# 1-Schematic_relay_module.net
KiCad netlist of a schematic drawn in EasyEDA
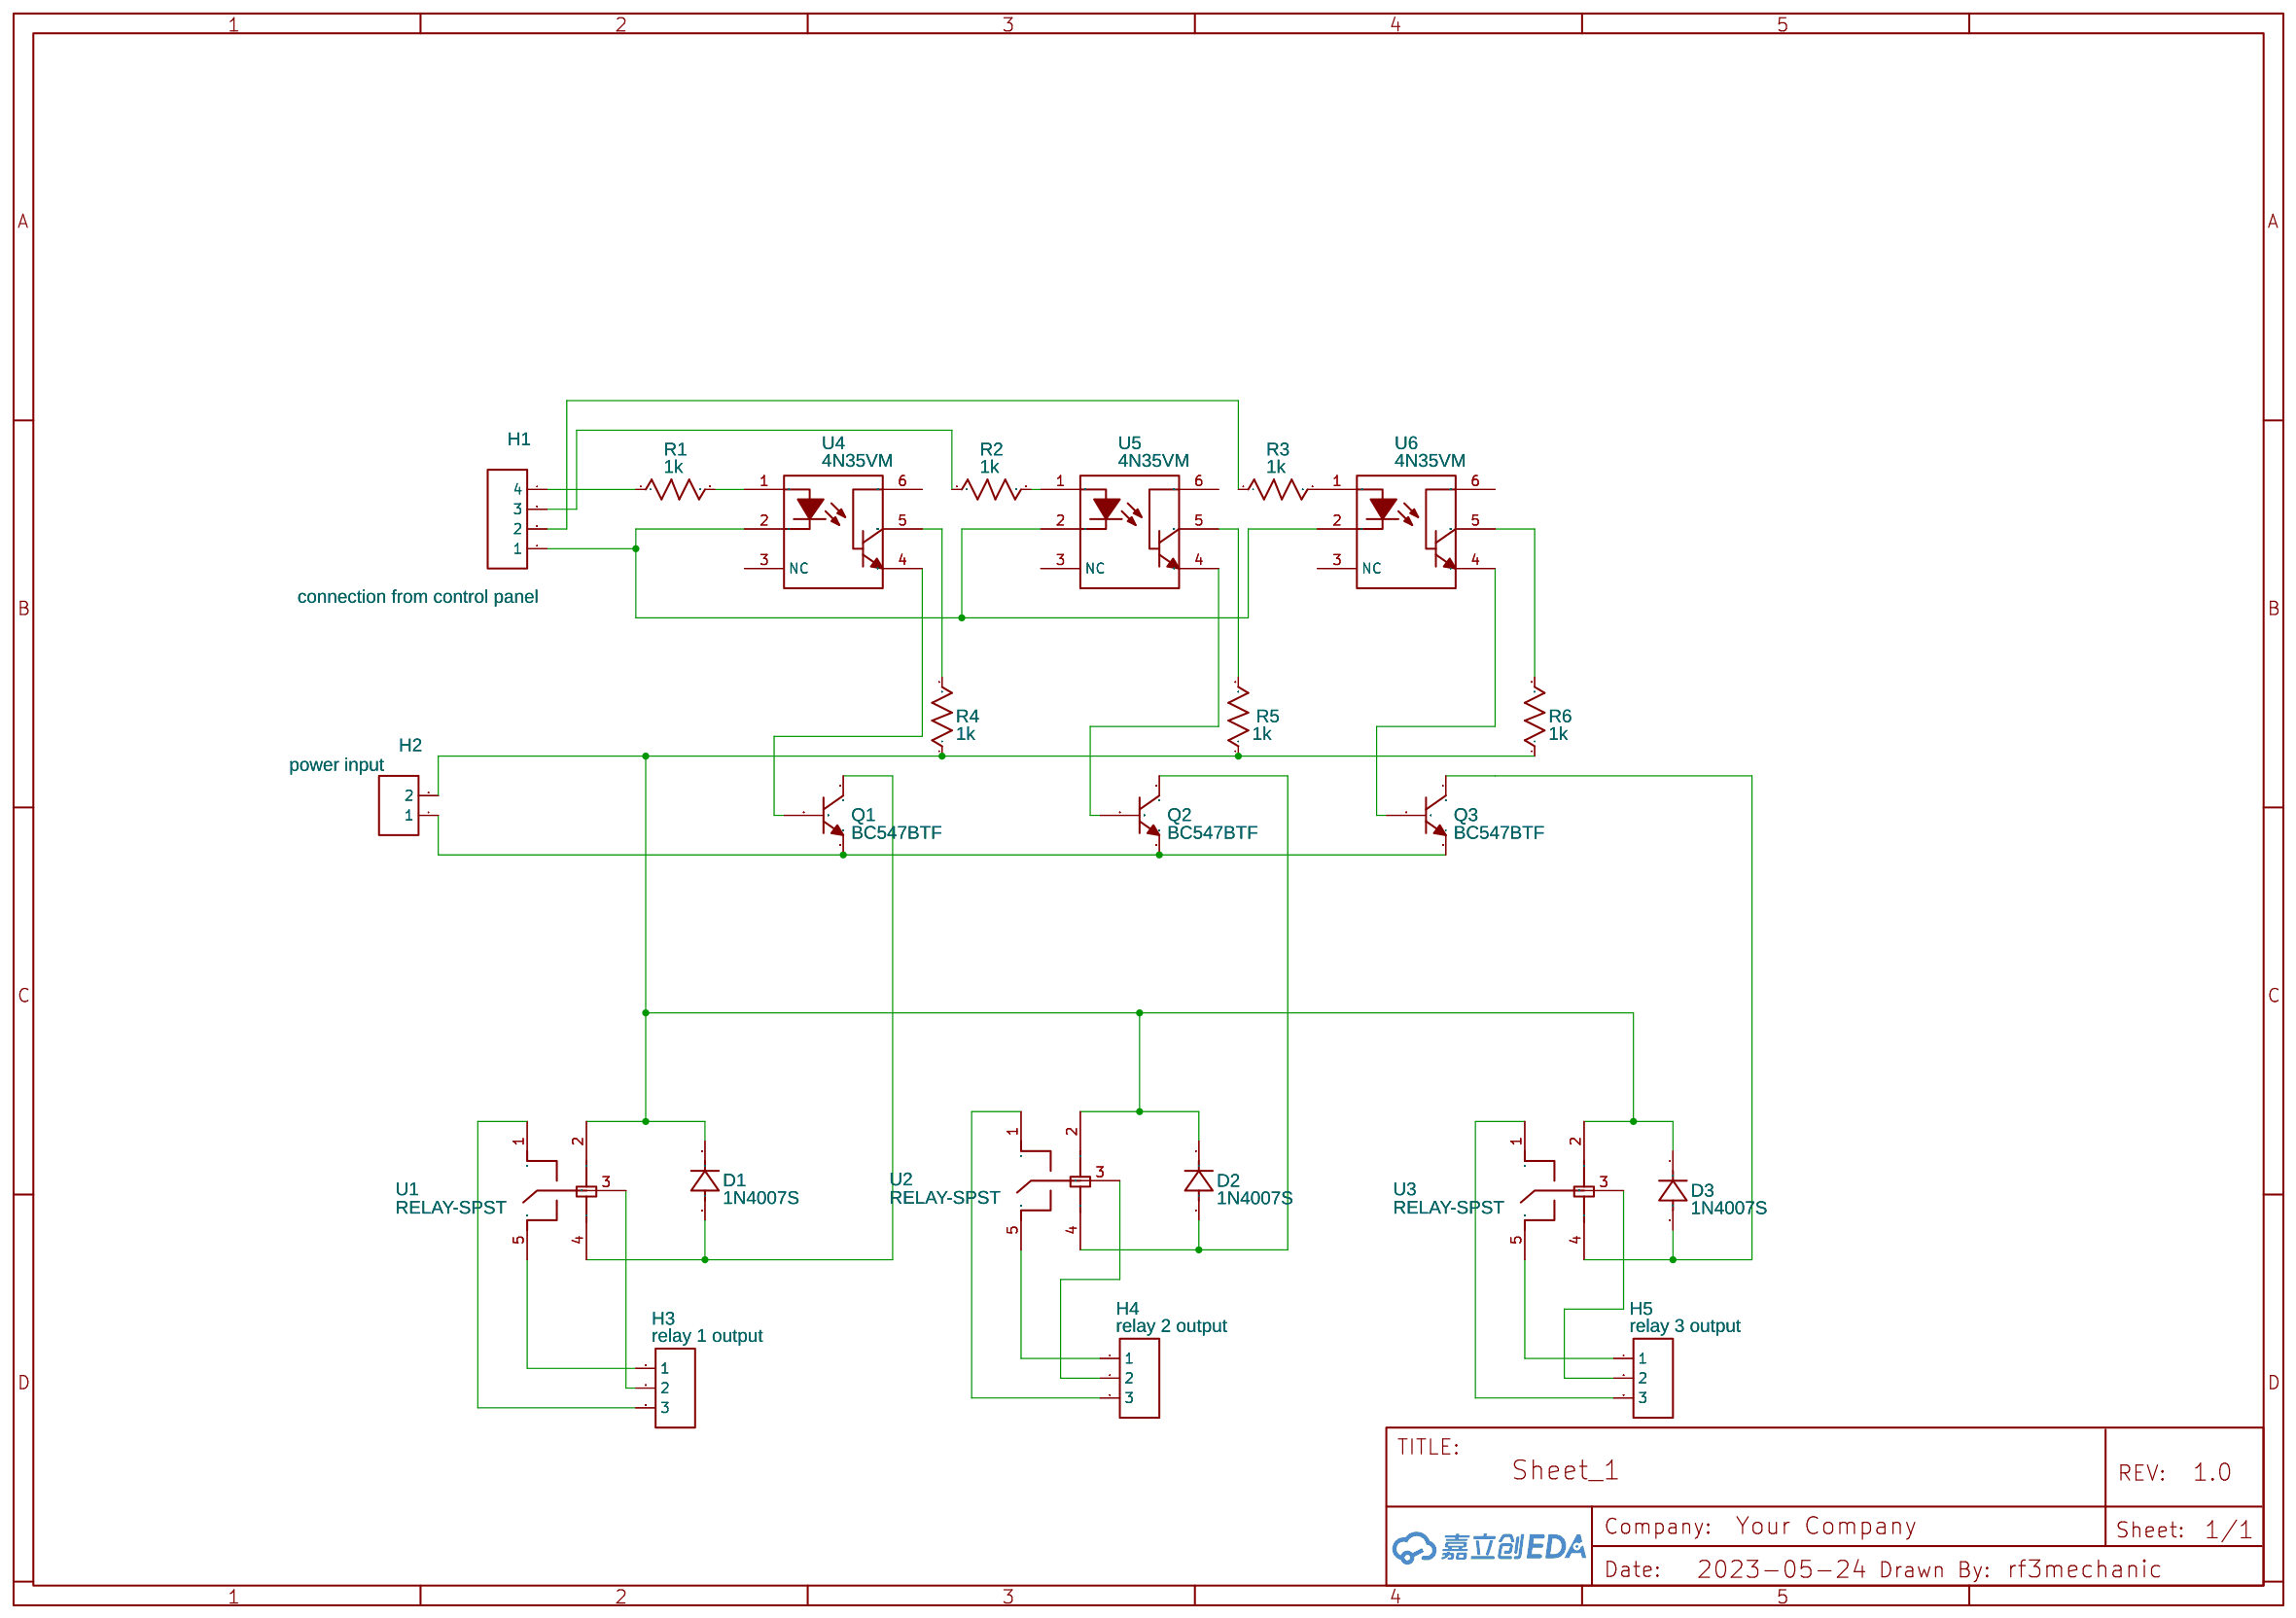
[diagram p0: schematic sheet]

(export (version "E")
  (design (tool "Eeschema 10.0.6"))
  (components
    (comp (ref "D1")
      (value "1N4007S")
      (fields (field (name "BOM_Supplier Part") "C2992088"))
      (libsource (lib "") (part "1N4007S"))
    )
    (comp (ref "D2")
      (value "1N4007S")
      (fields (field (name "BOM_Supplier Part") "C2992088"))
      (libsource (lib "") (part "1N4007S"))
    )
    (comp (ref "D3")
      (value "1N4007S")
      (fields (field (name "BOM_Supplier Part") "C2992088"))
      (libsource (lib "") (part "1N4007S"))
    )
    (comp (ref "H1")
      (value "connection from control panel")
      (fields (field (name "BOM_Supplier Part") "C225501"))
      (libsource (lib "") (part "HDR-F-2.54_1x4"))
    )
    (comp (ref "H2")
      (value "power input")
      (fields (field (name "BOM_Supplier Part") "C49661"))
      (libsource (lib "") (part "HDR-F-2.54_1x2"))
    )
    (comp (ref "H3")
      (value "relay 1 output")
      (fields (field (name "BOM_Supplier Part") "C146690"))
      (libsource (lib "") (part "HDR-F-2.54_1x3"))
    )
    (comp (ref "H4")
      (value "relay 2 output")
      (fields (field (name "BOM_Supplier Part") "C146690"))
      (libsource (lib "") (part "HDR-F-2.54_1x3"))
    )
    (comp (ref "H5")
      (value "relay 3 output")
      (fields (field (name "BOM_Supplier Part") "C146690"))
      (libsource (lib "") (part "HDR-F-2.54_1x3"))
    )
    (comp (ref "Q1")
      (value "BC547BTF")
      (fields (field (name "BOM_Supplier Part") "C900798"))
      (libsource (lib "") (part "BC547BTF"))
    )
    (comp (ref "Q2")
      (value "BC547BTF")
      (fields (field (name "BOM_Supplier Part") "C900798"))
      (libsource (lib "") (part "BC547BTF"))
    )
    (comp (ref "Q3")
      (value "BC547BTF")
      (fields (field (name "BOM_Supplier Part") "C900798"))
      (libsource (lib "") (part "BC547BTF"))
    )
    (comp (ref "R1") (value "1k") (libsource (lib "") (part "R_AXIAL-0.4_US")))
    (comp (ref "R2") (value "1k") (libsource (lib "") (part "R_AXIAL-0.4_US")))
    (comp (ref "R3") (value "1k") (libsource (lib "") (part "R_AXIAL-0.4_US")))
    (comp (ref "R4") (value "1k") (libsource (lib "") (part "R_AXIAL-0.4_US_1")))
    (comp (ref "R5") (value "1k") (libsource (lib "") (part "R_AXIAL-0.4_US_1")))
    (comp (ref "R6") (value "1k") (libsource (lib "") (part "R_AXIAL-0.4_US_1")))
    (comp (ref "U1")
      (value "RELAY-SPST")
      (fields
        (field (name "BOM_Manufacturer Part") "Relay-SPST")
        (field (name "BOM_Supplier Part") "C2941249")
      )
      (libsource (lib "") (part "RELAY-SPST"))
    )
    (comp (ref "U2")
      (value "RELAY-SPST")
      (fields
        (field (name "BOM_Manufacturer Part") "Relay-SPST")
        (field (name "BOM_Supplier Part") "C2941249")
      )
      (libsource (lib "") (part "RELAY-SPST"))
    )
    (comp (ref "U3")
      (value "RELAY-SPST")
      (fields
        (field (name "BOM_Manufacturer Part") "Relay-SPST")
        (field (name "BOM_Supplier Part") "C2941249")
      )
      (libsource (lib "") (part "RELAY-SPST"))
    )
    (comp (ref "U4")
      (value "4N35VM")
      (fields (field (name "BOM_Supplier Part") "C898968"))
      (libsource (lib "") (part "4N35VM"))
    )
    (comp (ref "U5")
      (value "4N35VM")
      (fields (field (name "BOM_Supplier Part") "C898968"))
      (libsource (lib "") (part "4N35VM"))
    )
    (comp (ref "U6")
      (value "4N35VM")
      (fields (field (name "BOM_Supplier Part") "C898968"))
      (libsource (lib "") (part "4N35VM"))
    )
  )
  (nets
    (net (code "1") (name "Net-(D1-A)") (class "Default")
      (node (ref "D1") (pin "2") (pinfunction "A_2") (pintype "unspecified"))
      (node (ref "Q1") (pin "1") (pinfunction "C_1") (pintype "unspecified"))
      (node (ref "U1") (pin "4") (pinfunction "4_4") (pintype "unspecified"))
    )
    (net (code "2") (name "Net-(D1-K)") (class "Default")
      (node (ref "D1") (pin "1") (pinfunction "K_1") (pintype "unspecified"))
      (node (ref "D2") (pin "1") (pinfunction "K_1") (pintype "unspecified"))
      (node (ref "D3") (pin "1") (pinfunction "K_1") (pintype "unspecified"))
      (node (ref "H2") (pin "2") (pinfunction "2_2") (pintype "input"))
      (node (ref "R4") (pin "1") (pinfunction "1_1") (pintype "unspecified"))
      (node (ref "R5") (pin "1") (pinfunction "1_1") (pintype "unspecified"))
      (node (ref "R6") (pin "1") (pinfunction "1_1") (pintype "unspecified"))
      (node (ref "U1") (pin "2") (pinfunction "2_2") (pintype "unspecified"))
      (node (ref "U2") (pin "2") (pinfunction "2_2") (pintype "unspecified"))
      (node (ref "U3") (pin "2") (pinfunction "2_2") (pintype "unspecified"))
    )
    (net (code "3") (name "Net-(D2-A)") (class "Default")
      (node (ref "D2") (pin "2") (pinfunction "A_2") (pintype "unspecified"))
      (node (ref "Q2") (pin "1") (pinfunction "C_1") (pintype "unspecified"))
      (node (ref "U2") (pin "4") (pinfunction "4_4") (pintype "unspecified"))
    )
    (net (code "4") (name "Net-(D3-A)") (class "Default")
      (node (ref "D3") (pin "2") (pinfunction "A_2") (pintype "unspecified"))
      (node (ref "Q3") (pin "1") (pinfunction "C_1") (pintype "unspecified"))
      (node (ref "U3") (pin "4") (pinfunction "4_4") (pintype "unspecified"))
    )
    (net (code "5") (name "Net-(H1-Pad2)") (class "Default")
      (node (ref "H1") (pin "2") (pinfunction "2_2") (pintype "unspecified"))
      (node (ref "R3") (pin "1") (pinfunction "1_1") (pintype "unspecified"))
    )
    (net (code "6") (name "Net-(H1-Pad3)") (class "Default")
      (node (ref "H1") (pin "3") (pinfunction "3_3") (pintype "unspecified"))
      (node (ref "R2") (pin "1") (pinfunction "1_1") (pintype "unspecified"))
    )
    (net (code "7") (name "Net-(H1-Pad4)") (class "Default")
      (node (ref "H1") (pin "4") (pinfunction "4_4") (pintype "unspecified"))
      (node (ref "R1") (pin "1") (pinfunction "1_1") (pintype "unspecified"))
    )
    (net (code "8") (name "Net-(H3-Pad1)") (class "Default")
      (node (ref "H3") (pin "1") (pinfunction "1_1") (pintype "input"))
      (node (ref "U1") (pin "5") (pinfunction "5_5") (pintype "unspecified"))
    )
    (net (code "9") (name "Net-(H3-Pad2)") (class "Default")
      (node (ref "H3") (pin "2") (pinfunction "2_2") (pintype "input"))
      (node (ref "U1") (pin "3") (pinfunction "3_3") (pintype "unspecified"))
    )
    (net (code "10") (name "Net-(H3-Pad3)") (class "Default")
      (node (ref "H3") (pin "3") (pinfunction "3_3") (pintype "input"))
      (node (ref "U1") (pin "1") (pinfunction "1_1") (pintype "unspecified"))
    )
    (net (code "11") (name "Net-(H4-Pad1)") (class "Default")
      (node (ref "H4") (pin "1") (pinfunction "1_1") (pintype "input"))
      (node (ref "U2") (pin "5") (pinfunction "5_5") (pintype "unspecified"))
    )
    (net (code "12") (name "Net-(H4-Pad2)") (class "Default")
      (node (ref "H4") (pin "2") (pinfunction "2_2") (pintype "input"))
      (node (ref "U2") (pin "3") (pinfunction "3_3") (pintype "unspecified"))
    )
    (net (code "13") (name "Net-(H4-Pad3)") (class "Default")
      (node (ref "H4") (pin "3") (pinfunction "3_3") (pintype "input"))
      (node (ref "U2") (pin "1") (pinfunction "1_1") (pintype "unspecified"))
    )
    (net (code "14") (name "Net-(H5-Pad1)") (class "Default")
      (node (ref "H5") (pin "1") (pinfunction "1_1") (pintype "input"))
      (node (ref "U3") (pin "5") (pinfunction "5_5") (pintype "unspecified"))
    )
    (net (code "15") (name "Net-(H5-Pad2)") (class "Default")
      (node (ref "H5") (pin "2") (pinfunction "2_2") (pintype "input"))
      (node (ref "U3") (pin "3") (pinfunction "3_3") (pintype "unspecified"))
    )
    (net (code "16") (name "Net-(H5-Pad3)") (class "Default")
      (node (ref "H5") (pin "3") (pinfunction "3_3") (pintype "input"))
      (node (ref "U3") (pin "1") (pinfunction "1_1") (pintype "unspecified"))
    )
    (net (code "17") (name "Net-(Q1-B)") (class "Default")
      (node (ref "Q1") (pin "2") (pinfunction "B_2") (pintype "unspecified"))
      (node (ref "U4") (pin "4") (pinfunction "EMI_4") (pintype "unspecified"))
    )
    (net (code "18") (name "Net-(Q1-E)") (class "Default")
      (node (ref "H2") (pin "1") (pinfunction "1_1") (pintype "input"))
      (node (ref "Q1") (pin "3") (pinfunction "E_3") (pintype "unspecified"))
      (node (ref "Q2") (pin "3") (pinfunction "E_3") (pintype "unspecified"))
      (node (ref "Q3") (pin "3") (pinfunction "E_3") (pintype "unspecified"))
    )
    (net (code "19") (name "Net-(Q2-B)") (class "Default")
      (node (ref "Q2") (pin "2") (pinfunction "B_2") (pintype "unspecified"))
      (node (ref "U5") (pin "4") (pinfunction "EMI_4") (pintype "unspecified"))
    )
    (net (code "20") (name "Net-(Q3-B)") (class "Default")
      (node (ref "Q3") (pin "2") (pinfunction "B_2") (pintype "unspecified"))
      (node (ref "U6") (pin "4") (pinfunction "EMI_4") (pintype "unspecified"))
    )
    (net (code "21") (name "Net-(U4-ANO)") (class "Default")
      (node (ref "R1") (pin "2") (pinfunction "2_2") (pintype "unspecified"))
      (node (ref "U4") (pin "1") (pinfunction "ANO_1") (pintype "unspecified"))
    )
    (net (code "22") (name "Net-(U4-CAT)") (class "Default")
      (node (ref "H1") (pin "1") (pinfunction "1_1") (pintype "unspecified"))
      (node (ref "U4") (pin "2") (pinfunction "CAT_2") (pintype "unspecified"))
      (node (ref "U5") (pin "2") (pinfunction "CAT_2") (pintype "unspecified"))
      (node (ref "U6") (pin "2") (pinfunction "CAT_2") (pintype "unspecified"))
    )
    (net (code "23") (name "Net-(U4-COL)") (class "Default")
      (node (ref "R4") (pin "2") (pinfunction "2_2") (pintype "unspecified"))
      (node (ref "U4") (pin "5") (pinfunction "COL_5") (pintype "unspecified"))
    )
    (net (code "24") (name "Net-(U5-ANO)") (class "Default")
      (node (ref "R2") (pin "2") (pinfunction "2_2") (pintype "unspecified"))
      (node (ref "U5") (pin "1") (pinfunction "ANO_1") (pintype "unspecified"))
    )
    (net (code "25") (name "Net-(U5-COL)") (class "Default")
      (node (ref "R5") (pin "2") (pinfunction "2_2") (pintype "unspecified"))
      (node (ref "U5") (pin "5") (pinfunction "COL_5") (pintype "unspecified"))
    )
    (net (code "26") (name "Net-(U6-ANO)") (class "Default")
      (node (ref "R3") (pin "2") (pinfunction "2_2") (pintype "unspecified"))
      (node (ref "U6") (pin "1") (pinfunction "ANO_1") (pintype "unspecified"))
    )
    (net (code "27") (name "Net-(U6-COL)") (class "Default")
      (node (ref "R6") (pin "2") (pinfunction "2_2") (pintype "unspecified"))
      (node (ref "U6") (pin "5") (pinfunction "COL_5") (pintype "unspecified"))
    )
    (net (code "28") (name "unconnected-(U4-BAS-Pad6)") (class "Default")
      (node (ref "U4") (pin "6") (pinfunction "BAS_6") (pintype "unspecified"))
    )
    (net (code "29") (name "unconnected-(U4-NC-Pad3)") (class "Default")
      (node (ref "U4") (pin "3") (pinfunction "NC_3") (pintype "unspecified"))
    )
    (net (code "30") (name "unconnected-(U5-BAS-Pad6)") (class "Default")
      (node (ref "U5") (pin "6") (pinfunction "BAS_6") (pintype "unspecified"))
    )
    (net (code "31") (name "unconnected-(U5-NC-Pad3)") (class "Default")
      (node (ref "U5") (pin "3") (pinfunction "NC_3") (pintype "unspecified"))
    )
    (net (code "32") (name "unconnected-(U6-BAS-Pad6)") (class "Default")
      (node (ref "U6") (pin "6") (pinfunction "BAS_6") (pintype "unspecified"))
    )
    (net (code "33") (name "unconnected-(U6-NC-Pad3)") (class "Default")
      (node (ref "U6") (pin "3") (pinfunction "NC_3") (pintype "unspecified"))
    )
  )
)
